# LowLatch.net
KiCad netlist of a schematic drawn in Altium Designer
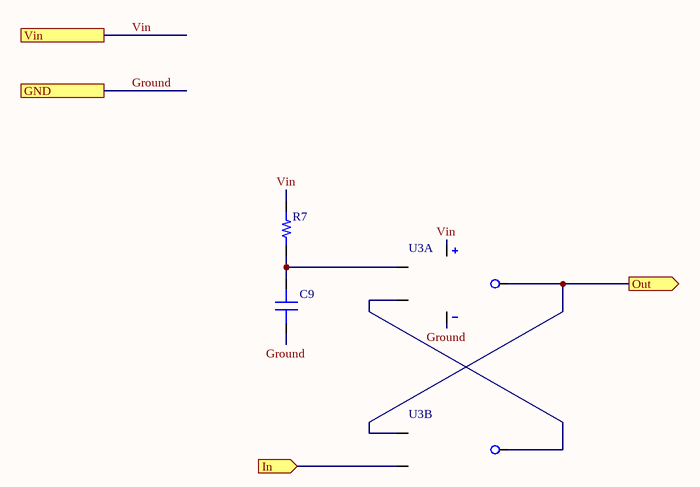
[diagram p0: LowLatch.SchDoc]

(export (version "E")
  (design (tool "Eeschema 10.0.6"))
  (components
    (comp (ref "C9")
      (value "capacitor")
      (footprint "0603")
      (description "Generic 0603 capacitor")
      (fields (field (name "VOLTAGE") "50"))
      (libsource (lib "altlib") (part "capacitor"))
    )
    (comp (ref "R7") (value "~") (footprint "RES 0603/1608") (libsource (lib "altlib") (part "Resistor")))
    (comp (ref "U3")
      (value "SN74LVC2G132DCUR")
      (footprint "R-PDSO-G8")
      (description "SN74LVC2G132DCUR 2channel NAND Gate")
      (fields (field (name "UPDATEDBY") "Kevin"))
      (libsource (lib "altlib") (part "SN74LVC2G132DCUR"))
    )
  )
  (nets
    (net (code "1") (name "/Ground") (class "Default")
      (node (ref "C9") (pin "2") (pinfunction "2_2") (pintype "passive"))
      (node (ref "U3") (pin "4") (pinfunction "GND_4") (pintype "passive"))
    )
    (net (code "2") (name "/In") (class "Default")
      (node (ref "U3") (pin "6") (pinfunction "2B_6") (pintype "passive"))
    )
    (net (code "3") (name "/Out") (class "Default")
      (node (ref "U3") (pin "5") (pinfunction "2A_5") (pintype "passive"))
      (node (ref "U3") (pin "7") (pinfunction "1Y_7") (pintype "passive"))
    )
    (net (code "4") (name "/Vin") (class "Default")
      (node (ref "R7") (pin "2") (pinfunction "2_2") (pintype "passive"))
      (node (ref "U3") (pin "8") (pinfunction "Vcc_8") (pintype "passive"))
    )
    (net (code "5") (name "Net-(U3A-1A)") (class "Default")
      (node (ref "C9") (pin "1") (pinfunction "1_1") (pintype "passive"))
      (node (ref "R7") (pin "1") (pinfunction "1_1") (pintype "passive"))
      (node (ref "U3") (pin "1") (pinfunction "1A_1") (pintype "passive"))
    )
    (net (code "6") (name "Net-(U3A-1B)") (class "Default")
      (node (ref "U3") (pin "2") (pinfunction "1B_2") (pintype "passive"))
      (node (ref "U3") (pin "3") (pinfunction "2Y_3") (pintype "passive"))
    )
  )
)
